# ProPrj_SaveMyBook_2026-05-25.net
KiCad netlist of a schematic drawn in EasyEDA Pro
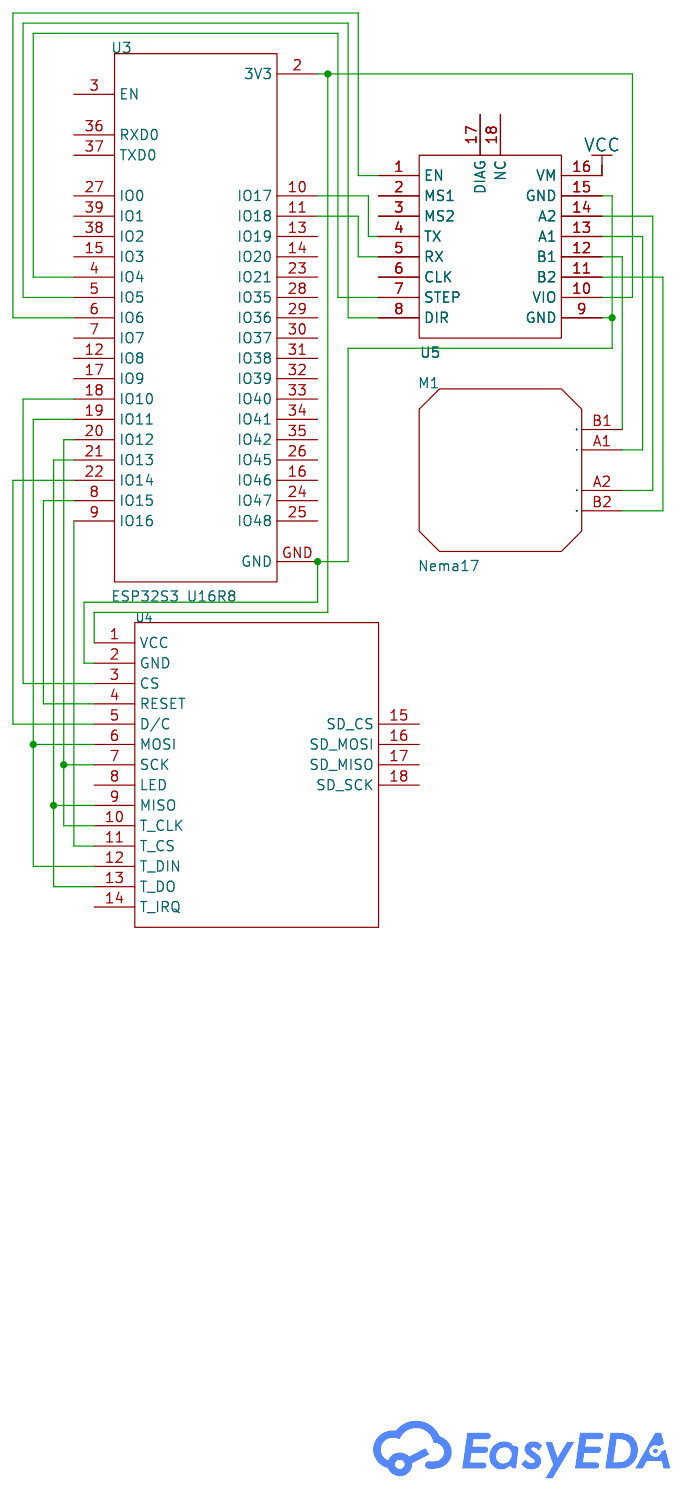
[diagram p0: schematic sheet]

(export (version "E")
  (design (tool "Eeschema 10.0.6"))
  (components
    (comp (ref "M1")
      (value "Nema17")
      (footprint "easyedapro:Nema Connector")
      (libsource (lib "easyedapro") (part "Nema17"))
    )
    (comp (ref "U3")
      (value "ESP32S3 U16R8")
      (footprint "easyedapro:ESP32S3")
      (libsource (lib "easyedapro") (part "ESP32S3"))
    )
    (comp (ref "U4")
      (value "~")
      (fields (field (name "Manufacturer Part") "LCD-TJCTM24028-SPI-2.8-inch"))
      (libsource (lib "easyedapro") (part "LCD-TJCTM24028-SPI-2.8-inch"))
    )
    (comp (ref "U5")
      (value "~")
      (footprint "easyedapro:TMC2209")
      (libsource (lib "easyedapro") (part "TMC2209"))
    )
  )
  (nets
    (net (code "1") (name "Net-(U3-3V3)") (class "Default")
      (node (ref "U3") (pin "2") (pinfunction "3V3_2") (pintype "unspecified"))
      (node (ref "U4") (pin "1") (pinfunction "VCC_1") (pintype "input"))
      (node (ref "U5") (pin "10") (pinfunction "VIO_10") (pintype "input"))
    )
    (net (code "2") (name "Net-(U3-IO4)") (class "Default")
      (node (ref "U3") (pin "4") (pinfunction "IO4_4") (pintype "bidirectional"))
      (node (ref "U5") (pin "7") (pinfunction "STEP_7") (pintype "input"))
    )
    (net (code "3") (name "Net-(U3-IO5)") (class "Default")
      (node (ref "U3") (pin "5") (pinfunction "IO5_5") (pintype "bidirectional"))
      (node (ref "U5") (pin "8") (pinfunction "DIR_8") (pintype "input"))
    )
    (net (code "4") (name "Net-(U3-IO6)") (class "Default")
      (node (ref "U3") (pin "6") (pinfunction "IO6_6") (pintype "bidirectional"))
      (node (ref "U5") (pin "1") (pinfunction "EN_1") (pintype "input"))
    )
    (net (code "5") (name "Net-(U3-IO10)") (class "Default")
      (node (ref "U3") (pin "18") (pinfunction "IO10_18") (pintype "bidirectional"))
      (node (ref "U4") (pin "3") (pinfunction "CS_3") (pintype "input"))
    )
    (net (code "6") (name "Net-(U3-IO11)") (class "Default")
      (node (ref "U3") (pin "19") (pinfunction "IO11_19") (pintype "bidirectional"))
      (node (ref "U4") (pin "12") (pinfunction "T_DIN_12") (pintype "input"))
      (node (ref "U4") (pin "6") (pinfunction "MOSI_6") (pintype "input"))
    )
    (net (code "7") (name "Net-(U3-IO12)") (class "Default")
      (node (ref "U3") (pin "20") (pinfunction "IO12_20") (pintype "bidirectional"))
      (node (ref "U4") (pin "10") (pinfunction "T_CLK_10") (pintype "input"))
      (node (ref "U4") (pin "7") (pinfunction "SCK_7") (pintype "input"))
    )
    (net (code "8") (name "Net-(U3-IO13)") (class "Default")
      (node (ref "U3") (pin "21") (pinfunction "IO13_21") (pintype "bidirectional"))
      (node (ref "U4") (pin "13") (pinfunction "T_DO_13") (pintype "input"))
      (node (ref "U4") (pin "9") (pinfunction "MISO_9") (pintype "input"))
    )
    (net (code "9") (name "Net-(U3-IO14)") (class "Default")
      (node (ref "U3") (pin "22") (pinfunction "IO14_22") (pintype "bidirectional"))
      (node (ref "U4") (pin "5") (pinfunction "D/C_5") (pintype "input"))
    )
    (net (code "10") (name "Net-(U3-IO15)") (class "Default")
      (node (ref "U3") (pin "8") (pinfunction "IO15_8") (pintype "bidirectional"))
      (node (ref "U4") (pin "4") (pinfunction "RESET_4") (pintype "input"))
    )
    (net (code "11") (name "Net-(U3-IO16)") (class "Default")
      (node (ref "U3") (pin "9") (pinfunction "IO16_9") (pintype "bidirectional"))
      (node (ref "U4") (pin "11") (pinfunction "T_CS_11") (pintype "input"))
    )
    (net (code "12") (name "Net-(U3-IO17)") (class "Default")
      (node (ref "U3") (pin "10") (pinfunction "IO17_10") (pintype "bidirectional"))
      (node (ref "U5") (pin "4") (pinfunction "TX_4") (pintype "input"))
    )
    (net (code "13") (name "Net-(U3-IO18)") (class "Default")
      (node (ref "U3") (pin "11") (pinfunction "IO18_11") (pintype "bidirectional"))
      (node (ref "U5") (pin "5") (pinfunction "RX_5") (pintype "input"))
    )
    (net (code "14") (name "Net-(U4-GND)") (class "Default")
      (node (ref "U3") (pin "GND") (pinfunction "GND_GND") (pintype "unspecified"))
      (node (ref "U4") (pin "2") (pinfunction "GND_2") (pintype "input"))
      (node (ref "U5") (pin "15") (pinfunction "GND_15") (pintype "input"))
      (node (ref "U5") (pin "9") (pinfunction "GND_9") (pintype "input"))
    )
    (net (code "15") (name "Net-(U5-A1)") (class "Default")
      (node (ref "M1") (pin "A1") (pinfunction "A1_A1") (pintype "unspecified"))
      (node (ref "U5") (pin "13") (pinfunction "A1_13") (pintype "input"))
    )
    (net (code "16") (name "Net-(U5-A2)") (class "Default")
      (node (ref "M1") (pin "A2") (pinfunction "A2_A2") (pintype "unspecified"))
      (node (ref "U5") (pin "14") (pinfunction "A2_14") (pintype "input"))
    )
    (net (code "17") (name "Net-(U5-B1)") (class "Default")
      (node (ref "M1") (pin "B1") (pinfunction "B1_B1") (pintype "unspecified"))
      (node (ref "U5") (pin "12") (pinfunction "B1_12") (pintype "input"))
    )
    (net (code "18") (name "Net-(U5-B2)") (class "Default")
      (node (ref "M1") (pin "B2") (pinfunction "B2_B2") (pintype "unspecified"))
      (node (ref "U5") (pin "11") (pinfunction "B2_11") (pintype "input"))
    )
    (net (code "19") (name "VCC") (class "Default")
      (node (ref "U5") (pin "16") (pinfunction "VM_16") (pintype "input"))
    )
    (net (code "20") (name "unconnected-(U3-EN-Pad3)") (class "Default")
      (node (ref "U3") (pin "3") (pinfunction "EN_3") (pintype "input"))
    )
    (net (code "21") (name "unconnected-(U3-IO0-Pad27)") (class "Default")
      (node (ref "U3") (pin "27") (pinfunction "IO0_27") (pintype "bidirectional"))
    )
    (net (code "22") (name "unconnected-(U3-IO1-Pad39)") (class "Default")
      (node (ref "U3") (pin "39") (pinfunction "IO1_39") (pintype "bidirectional"))
    )
    (net (code "23") (name "unconnected-(U3-IO2-Pad38)") (class "Default")
      (node (ref "U3") (pin "38") (pinfunction "IO2_38") (pintype "bidirectional"))
    )
    (net (code "24") (name "unconnected-(U3-IO3-Pad15)") (class "Default")
      (node (ref "U3") (pin "15") (pinfunction "IO3_15") (pintype "bidirectional"))
    )
    (net (code "25") (name "unconnected-(U3-IO7-Pad7)") (class "Default")
      (node (ref "U3") (pin "7") (pinfunction "IO7_7") (pintype "bidirectional"))
    )
    (net (code "26") (name "unconnected-(U3-IO8-Pad12)") (class "Default")
      (node (ref "U3") (pin "12") (pinfunction "IO8_12") (pintype "bidirectional"))
    )
    (net (code "27") (name "unconnected-(U3-IO9-Pad17)") (class "Default")
      (node (ref "U3") (pin "17") (pinfunction "IO9_17") (pintype "bidirectional"))
    )
    (net (code "28") (name "unconnected-(U3-IO19-Pad13)") (class "Default")
      (node (ref "U3") (pin "13") (pinfunction "IO19_13") (pintype "bidirectional"))
    )
    (net (code "29") (name "unconnected-(U3-IO20-Pad14)") (class "Default")
      (node (ref "U3") (pin "14") (pinfunction "IO20_14") (pintype "bidirectional"))
    )
    (net (code "30") (name "unconnected-(U3-IO21-Pad23)") (class "Default")
      (node (ref "U3") (pin "23") (pinfunction "IO21_23") (pintype "bidirectional"))
    )
    (net (code "31") (name "unconnected-(U3-IO35-Pad28)") (class "Default")
      (node (ref "U3") (pin "28") (pinfunction "IO35_28") (pintype "bidirectional"))
    )
    (net (code "32") (name "unconnected-(U3-IO36-Pad29)") (class "Default")
      (node (ref "U3") (pin "29") (pinfunction "IO36_29") (pintype "bidirectional"))
    )
    (net (code "33") (name "unconnected-(U3-IO37-Pad30)") (class "Default")
      (node (ref "U3") (pin "30") (pinfunction "IO37_30") (pintype "bidirectional"))
    )
    (net (code "34") (name "unconnected-(U3-IO38-Pad31)") (class "Default")
      (node (ref "U3") (pin "31") (pinfunction "IO38_31") (pintype "bidirectional"))
    )
    (net (code "35") (name "unconnected-(U3-IO39-Pad32)") (class "Default")
      (node (ref "U3") (pin "32") (pinfunction "IO39_32") (pintype "bidirectional"))
    )
    (net (code "36") (name "unconnected-(U3-IO40-Pad33)") (class "Default")
      (node (ref "U3") (pin "33") (pinfunction "IO40_33") (pintype "bidirectional"))
    )
    (net (code "37") (name "unconnected-(U3-IO41-Pad34)") (class "Default")
      (node (ref "U3") (pin "34") (pinfunction "IO41_34") (pintype "bidirectional"))
    )
    (net (code "38") (name "unconnected-(U3-IO42-Pad35)") (class "Default")
      (node (ref "U3") (pin "35") (pinfunction "IO42_35") (pintype "bidirectional"))
    )
    (net (code "39") (name "unconnected-(U3-IO45-Pad26)") (class "Default")
      (node (ref "U3") (pin "26") (pinfunction "IO45_26") (pintype "bidirectional"))
    )
    (net (code "40") (name "unconnected-(U3-IO46-Pad16)") (class "Default")
      (node (ref "U3") (pin "16") (pinfunction "IO46_16") (pintype "bidirectional"))
    )
    (net (code "41") (name "unconnected-(U3-IO47-Pad24)") (class "Default")
      (node (ref "U3") (pin "24") (pinfunction "IO47_24") (pintype "bidirectional"))
    )
    (net (code "42") (name "unconnected-(U3-IO48-Pad25)") (class "Default")
      (node (ref "U3") (pin "25") (pinfunction "IO48_25") (pintype "bidirectional"))
    )
    (net (code "43") (name "unconnected-(U3-RXD0-Pad36)") (class "Default")
      (node (ref "U3") (pin "36") (pinfunction "RXD0_36") (pintype "bidirectional"))
    )
    (net (code "44") (name "unconnected-(U3-TXD0-Pad37)") (class "Default")
      (node (ref "U3") (pin "37") (pinfunction "TXD0_37") (pintype "bidirectional"))
    )
    (net (code "45") (name "unconnected-(U4-LED-Pad8)") (class "Default")
      (node (ref "U4") (pin "8") (pinfunction "LED_8") (pintype "input"))
    )
    (net (code "46") (name "unconnected-(U4-SD_CS-Pad15)") (class "Default")
      (node (ref "U4") (pin "15") (pinfunction "SD_CS_15") (pintype "input"))
    )
    (net (code "47") (name "unconnected-(U4-SD_MISO-Pad17)") (class "Default")
      (node (ref "U4") (pin "17") (pinfunction "SD_MISO_17") (pintype "input"))
    )
    (net (code "48") (name "unconnected-(U4-SD_MOSI-Pad16)") (class "Default")
      (node (ref "U4") (pin "16") (pinfunction "SD_MOSI_16") (pintype "input"))
    )
    (net (code "49") (name "unconnected-(U4-SD_SCK-Pad18)") (class "Default")
      (node (ref "U4") (pin "18") (pinfunction "SD_SCK_18") (pintype "input"))
    )
    (net (code "50") (name "unconnected-(U4-T_IRQ-Pad14)") (class "Default")
      (node (ref "U4") (pin "14") (pinfunction "T_IRQ_14") (pintype "input"))
    )
    (net (code "51") (name "unconnected-(U5-CLK-Pad6)") (class "Default")
      (node (ref "U5") (pin "6") (pinfunction "CLK_6") (pintype "input"))
    )
    (net (code "52") (name "unconnected-(U5-DIAG-Pad17)") (class "Default")
      (node (ref "U5") (pin "17") (pinfunction "DIAG_17") (pintype "input"))
    )
    (net (code "53") (name "unconnected-(U5-MS1-Pad2)") (class "Default")
      (node (ref "U5") (pin "2") (pinfunction "MS1_2") (pintype "input"))
    )
    (net (code "54") (name "unconnected-(U5-MS2-Pad3)") (class "Default")
      (node (ref "U5") (pin "3") (pinfunction "MS2_3") (pintype "input"))
    )
    (net (code "55") (name "unconnected-(U5-NC-Pad18)") (class "Default")
      (node (ref "U5") (pin "18") (pinfunction "NC_18") (pintype "input"))
    )
  )
)
